# ESP32_USBC.net
KiCad netlist of a schematic drawn in Altium Designer
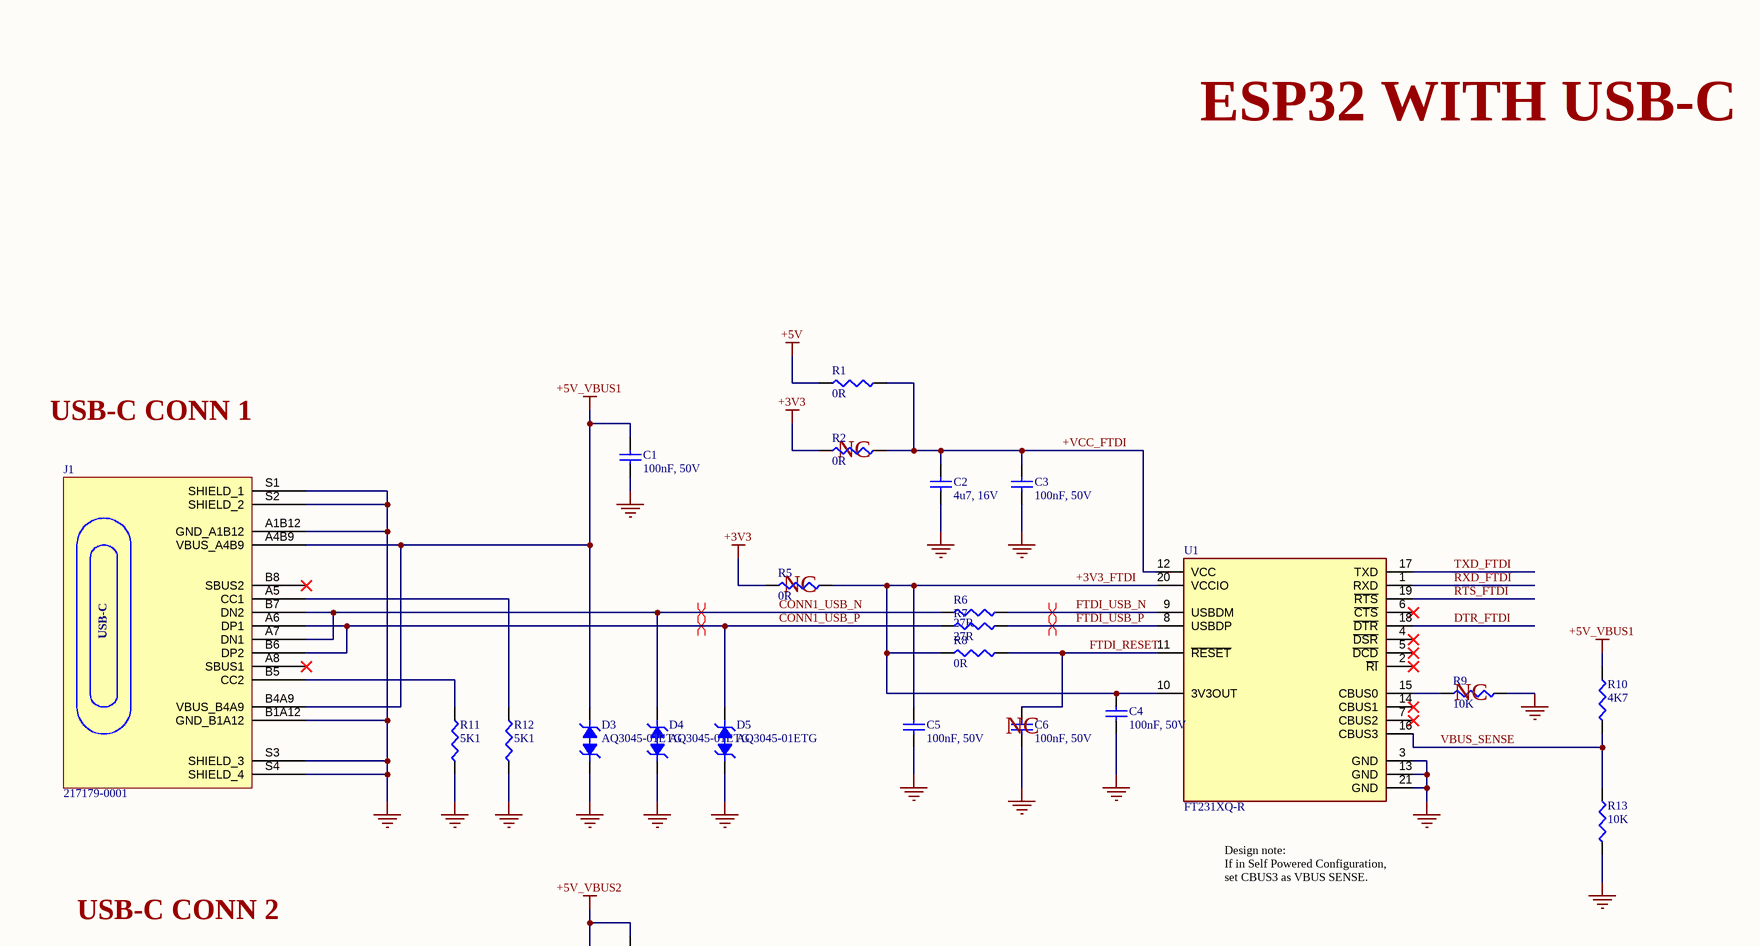
[diagram p0: ESP32_USBC.SchDoc, top left]
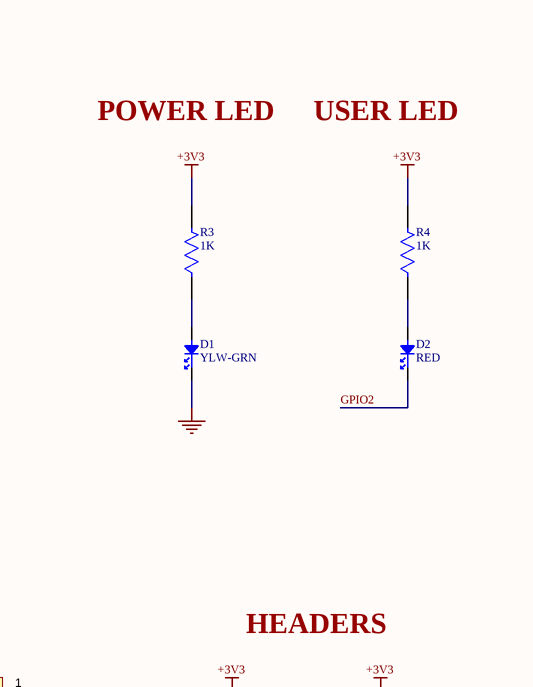
[diagram p1: ESP32_USBC.SchDoc, top right]
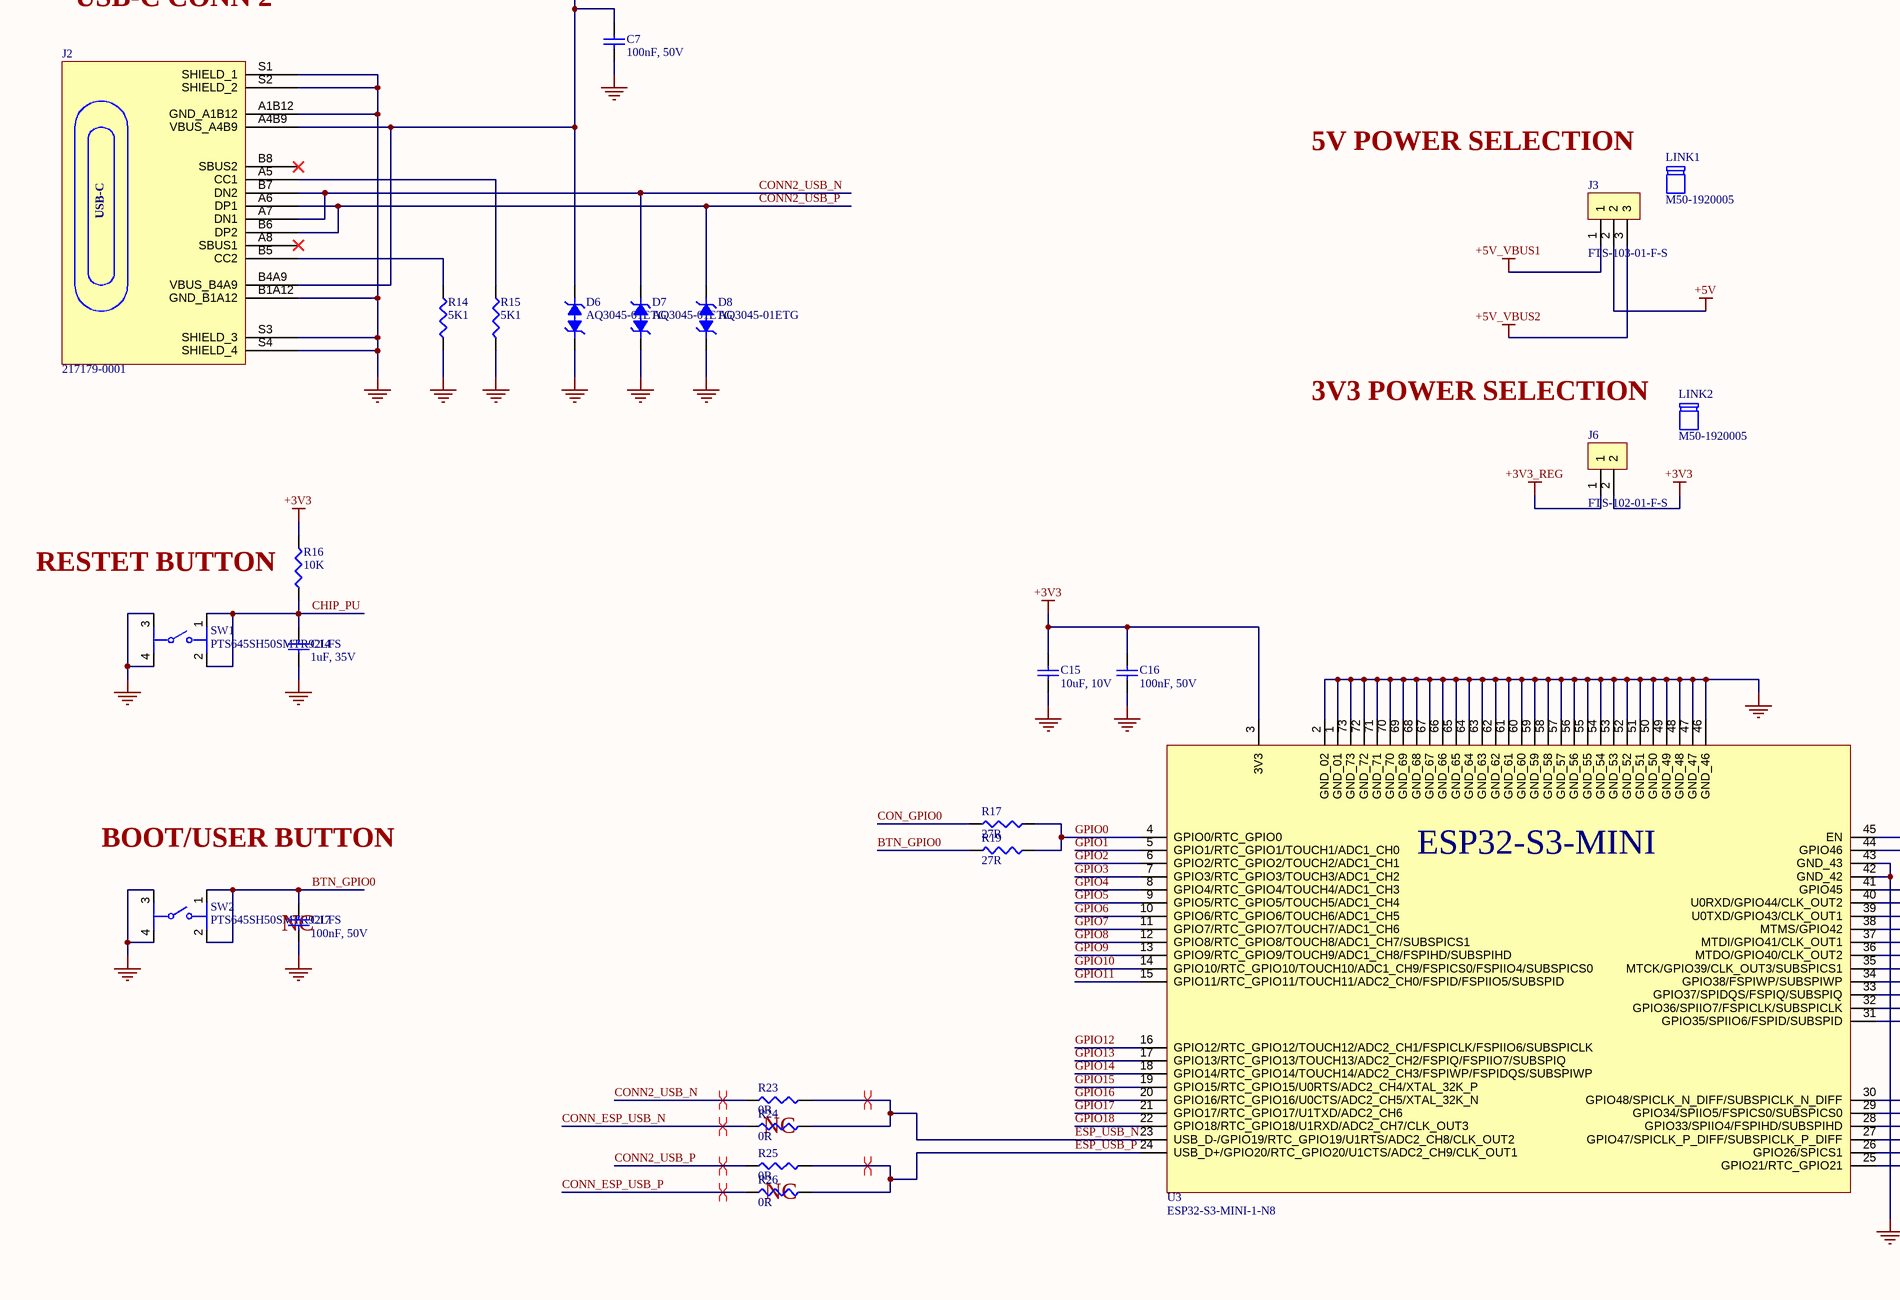
[diagram p2: ESP32_USBC.SchDoc, bottom left]
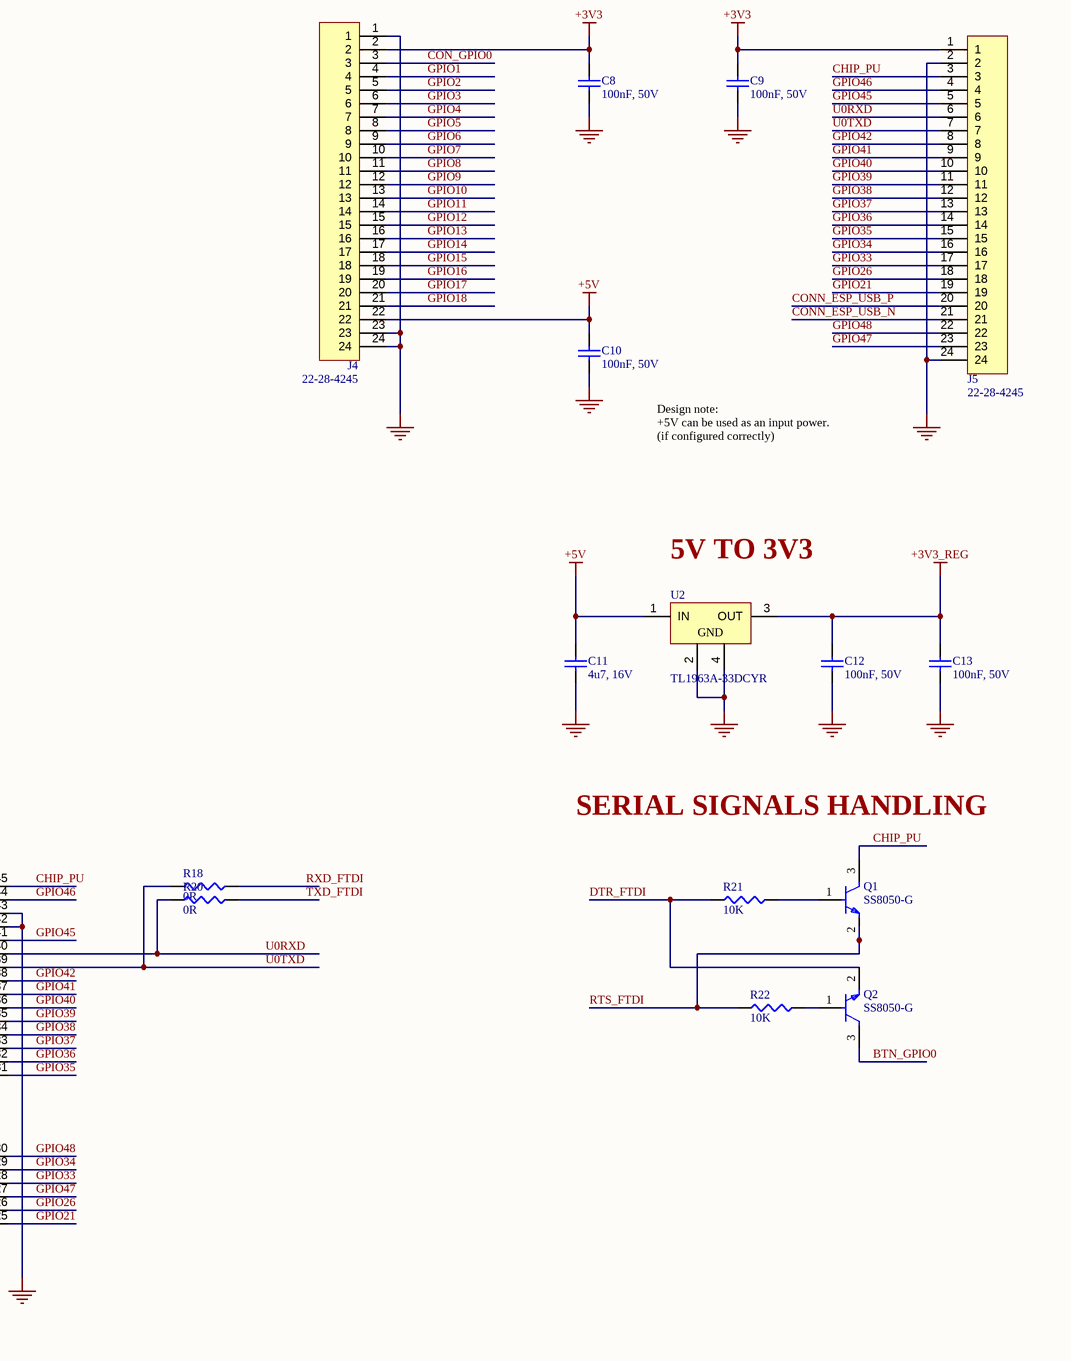
[diagram p3: ESP32_USBC.SchDoc, bottom right]

(export (version "E")
  (design (tool "Eeschema 10.0.6"))
  (components
    (comp (ref "C1")
      (value "100nF, 50V")
      (footprint "CAPC1005X65N")
      (description "CAP CER 0.1UF 50V X7R 0402")
      (fields
        (field (name "MANUFACTURER") "Samsung Electro-Mechanics")
        (field (name "MANUFACTURER PART NUMBER") "CL05B104KB5NNNC")
      )
      (libsource (lib "Schlib") (part "CL05B104KB5NNNC"))
    )
    (comp (ref "C2")
      (value "4u7, 16V")
      (footprint "CAPC1005X65N")
      (description "CAP CER 4.7UF 16V X5R 0402")
      (fields
        (field (name "MANUFACTURER") "Samsung Electro-Mechanics")
        (field (name "MANUFACTURER PART NUMBER") "CL05A475MO5NUNC")
      )
      (libsource (lib "Schlib") (part "CL05A475MO5NUNC"))
    )
    (comp (ref "C3")
      (value "100nF, 50V")
      (footprint "CAPC1005X65N")
      (description "CAP CER 0.1UF 50V X7R 0402")
      (fields
        (field (name "MANUFACTURER") "Samsung Electro-Mechanics")
        (field (name "MANUFACTURER PART NUMBER") "CL05B104KB5NNNC")
      )
      (libsource (lib "Schlib") (part "CL05B104KB5NNNC"))
    )
    (comp (ref "C4")
      (value "100nF, 50V")
      (footprint "CAPC1005X65N")
      (description "CAP CER 0.1UF 50V X7R 0402")
      (fields
        (field (name "MANUFACTURER") "Samsung Electro-Mechanics")
        (field (name "MANUFACTURER PART NUMBER") "CL05B104KB5NNNC")
      )
      (libsource (lib "Schlib") (part "CL05B104KB5NNNC"))
    )
    (comp (ref "C5")
      (value "100nF, 50V")
      (footprint "CAPC1005X65N")
      (description "CAP CER 0.1UF 50V X7R 0402")
      (fields
        (field (name "MANUFACTURER") "Samsung Electro-Mechanics")
        (field (name "MANUFACTURER PART NUMBER") "CL05B104KB5NNNC")
      )
      (libsource (lib "Schlib") (part "CL05B104KB5NNNC"))
    )
    (comp (ref "C6")
      (value "100nF, 50V")
      (footprint "CAPC1005X65N")
      (description "CAP CER 0.1UF 50V X7R 0402")
      (fields
        (field (name "MANUFACTURER") "Samsung Electro-Mechanics")
        (field (name "MANUFACTURER PART NUMBER") "CL05B104KB5NNNC")
      )
      (libsource (lib "Schlib") (part "CL05B104KB5NNNC"))
    )
    (comp (ref "C7")
      (value "100nF, 50V")
      (footprint "CAPC1005X65N")
      (description "CAP CER 0.1UF 50V X7R 0402")
      (fields
        (field (name "MANUFACTURER") "Samsung Electro-Mechanics")
        (field (name "MANUFACTURER PART NUMBER") "CL05B104KB5NNNC")
      )
      (libsource (lib "Schlib") (part "CL05B104KB5NNNC"))
    )
    (comp (ref "C8")
      (value "100nF, 50V")
      (footprint "CAPC1005X65N")
      (description "CAP CER 0.1UF 50V X7R 0402")
      (fields
        (field (name "MANUFACTURER") "Samsung Electro-Mechanics")
        (field (name "MANUFACTURER PART NUMBER") "CL05B104KB5NNNC")
      )
      (libsource (lib "Schlib") (part "CL05B104KB5NNNC"))
    )
    (comp (ref "C9")
      (value "100nF, 50V")
      (footprint "CAPC1005X65N")
      (description "CAP CER 0.1UF 50V X7R 0402")
      (fields
        (field (name "MANUFACTURER") "Samsung Electro-Mechanics")
        (field (name "MANUFACTURER PART NUMBER") "CL05B104KB5NNNC")
      )
      (libsource (lib "Schlib") (part "CL05B104KB5NNNC"))
    )
    (comp (ref "C10")
      (value "100nF, 50V")
      (footprint "CAPC1005X65N")
      (description "CAP CER 0.1UF 50V X7R 0402")
      (fields
        (field (name "MANUFACTURER") "Samsung Electro-Mechanics")
        (field (name "MANUFACTURER PART NUMBER") "CL05B104KB5NNNC")
      )
      (libsource (lib "Schlib") (part "CL05B104KB5NNNC"))
    )
    (comp (ref "C11")
      (value "4u7, 16V")
      (footprint "CAPC1005X65N")
      (description "CAP CER 4.7UF 16V X5R 0402")
      (fields
        (field (name "MANUFACTURER") "Samsung Electro-Mechanics")
        (field (name "MANUFACTURER PART NUMBER") "CL05A475MO5NUNC")
      )
      (libsource (lib "Schlib") (part "CL05A475MO5NUNC"))
    )
    (comp (ref "C12")
      (value "100nF, 50V")
      (footprint "CAPC1005X65N")
      (description "CAP CER 0.1UF 50V X7R 0402")
      (fields
        (field (name "MANUFACTURER") "Samsung Electro-Mechanics")
        (field (name "MANUFACTURER PART NUMBER") "CL05B104KB5NNNC")
      )
      (libsource (lib "Schlib") (part "CL05B104KB5NNNC"))
    )
    (comp (ref "C13")
      (value "100nF, 50V")
      (footprint "CAPC1005X65N")
      (description "CAP CER 0.1UF 50V X7R 0402")
      (fields
        (field (name "MANUFACTURER") "Samsung Electro-Mechanics")
        (field (name "MANUFACTURER PART NUMBER") "CL05B104KB5NNNC")
      )
      (libsource (lib "Schlib") (part "CL05B104KB5NNNC"))
    )
    (comp (ref "C14")
      (value "1uF, 35V")
      (footprint "CAPC1005X65N")
      (description "CAP CER 1UF 35V X5R 0402")
      (fields
        (field (name "MANUFACTURER") "Samsung Electro-Mechanics")
        (field (name "MANUFACTURER PART NUMBER") "CL05A105KL5NRNC")
      )
      (libsource (lib "Schlib") (part "CL05A105KL5NRNC"))
    )
    (comp (ref "C15")
      (value "10uF, 10V")
      (footprint "CAPC1005X65N")
      (description "CAP CER 10UF 10V X5R 0402")
      (fields
        (field (name "MANUFACTURER") "Samsung Electro-Mechanics")
        (field (name "MANUFACTURER PART NUMBER") "CL05A106MP8NUB8")
      )
      (libsource (lib "Schlib") (part "CL05A106MP8NUB8"))
    )
    (comp (ref "C16")
      (value "100nF, 50V")
      (footprint "CAPC1005X65N")
      (description "CAP CER 0.1UF 50V X7R 0402")
      (fields
        (field (name "MANUFACTURER") "Samsung Electro-Mechanics")
        (field (name "MANUFACTURER PART NUMBER") "CL05B104KB5NNNC")
      )
      (libsource (lib "Schlib") (part "CL05B104KB5NNNC"))
    )
    (comp (ref "C17")
      (value "100nF, 50V")
      (footprint "CAPC1005X65N")
      (description "CAP CER 0.1UF 50V X7R 0402")
      (fields
        (field (name "MANUFACTURER") "Samsung Electro-Mechanics")
        (field (name "MANUFACTURER PART NUMBER") "CL05B104KB5NNNC")
      )
      (libsource (lib "Schlib") (part "CL05B104KB5NNNC"))
    )
    (comp (ref "D1")
      (value "YLW-GRN")
      (footprint "LED0402G")
      (description "LED YLW-GRN 0402 SMD")
      (fields
        (field (name "MANUFACTURER") "Vishay")
        (field (name "MANUFACTURER PART NUMBER") "VLMG1500-GS08")
      )
      (libsource (lib "Schlib") (part "VLMG1500-GS08"))
    )
    (comp (ref "D2")
      (value "RED")
      (footprint "LED0402R")
      (description "LED RED 0402 SMD")
      (fields
        (field (name "MANUFACTURER") "Vishay")
        (field (name "MANUFACTURER PART NUMBER") "VLMS1500-GS08")
      )
      (libsource (lib "Schlib") (part "VLMS1500-GS08"))
    )
    (comp (ref "D3")
      (value "AQ3045-01ETG")
      (footprint "SOD882")
      (description "TVS DIODE 5.3VWM 12VC SOD882")
      (fields (field (name "MANUFACTURER") "Littelfuse") (field (name "LCSC PART NUMBER") "C3710326"))
      (libsource (lib "Schlib") (part "AQ3045-01ETG"))
    )
    (comp (ref "D4")
      (value "AQ3045-01ETG")
      (footprint "SOD882")
      (description "TVS DIODE 5.3VWM 12VC SOD882")
      (fields (field (name "MANUFACTURER") "Littelfuse") (field (name "LCSC PART NUMBER") "C3710326"))
      (libsource (lib "Schlib") (part "AQ3045-01ETG"))
    )
    (comp (ref "D5")
      (value "AQ3045-01ETG")
      (footprint "SOD882")
      (description "TVS DIODE 5.3VWM 12VC SOD882")
      (fields (field (name "MANUFACTURER") "Littelfuse") (field (name "LCSC PART NUMBER") "C3710326"))
      (libsource (lib "Schlib") (part "AQ3045-01ETG"))
    )
    (comp (ref "D6")
      (value "AQ3045-01ETG")
      (footprint "SOD882")
      (description "TVS DIODE 5.3VWM 12VC SOD882")
      (fields (field (name "MANUFACTURER") "Littelfuse") (field (name "LCSC PART NUMBER") "C3710326"))
      (libsource (lib "Schlib") (part "AQ3045-01ETG"))
    )
    (comp (ref "D7")
      (value "AQ3045-01ETG")
      (footprint "SOD882")
      (description "TVS DIODE 5.3VWM 12VC SOD882")
      (fields (field (name "MANUFACTURER") "Littelfuse") (field (name "LCSC PART NUMBER") "C3710326"))
      (libsource (lib "Schlib") (part "AQ3045-01ETG"))
    )
    (comp (ref "D8")
      (value "AQ3045-01ETG")
      (footprint "SOD882")
      (description "TVS DIODE 5.3VWM 12VC SOD882")
      (fields (field (name "MANUFACTURER") "Littelfuse") (field (name "LCSC PART NUMBER") "C3710326"))
      (libsource (lib "Schlib") (part "AQ3045-01ETG"))
    )
    (comp (ref "J1")
      (value "217179-0001")
      (footprint "FP-2171790001-MFG")
      (description "CONN RCP USB2.0 TYP C 24P SMD RA")
      (fields (field (name "MANUFACTURER") "Molex") (field (name "LCSC PART NUMBER") "C3197684"))
      (libsource (lib "Schlib") (part "217179-0001"))
    )
    (comp (ref "J2")
      (value "217179-0001")
      (footprint "FP-2171790001-MFG")
      (description "CONN RCP USB2.0 TYP C 24P SMD RA")
      (fields (field (name "MANUFACTURER") "Molex") (field (name "LCSC PART NUMBER") "C3197684"))
      (libsource (lib "Schlib") (part "217179-0001"))
    )
    (comp (ref "J3")
      (value "FTS-103-01-F-S")
      (footprint "HDR_1X3_1.27MM")
      (description "CONN HEADER VERT 3POS 1.27MM")
      (fields (field (name "MANUFACTURER") "Samtec") (field (name "LCSC PART NUMBER") "C3333578"))
      (libsource (lib "Schlib") (part "FTS-103-01-F-S"))
    )
    (comp (ref "J4")
      (value "22-28-4245")
      (footprint "HDR_1X24_2.54MM")
      (description "Connector Header Through Hole 24 position 0.100\" (2.54mm)")
      (fields (field (name "MANUFACTURER") "Molex") (field (name "LCSC PART NUMBER") "C7145888"))
      (libsource (lib "Schlib") (part "22-28-4245"))
    )
    (comp (ref "J5")
      (value "22-28-4245")
      (footprint "HDR_1X24_2.54MM")
      (description "Connector Header Through Hole 24 position 0.100\" (2.54mm)")
      (fields (field (name "MANUFACTURER") "Molex") (field (name "LCSC PART NUMBER") "C7145888"))
      (libsource (lib "") (part "22-28-4245_1"))
    )
    (comp (ref "J6")
      (value "FTS-102-01-F-S")
      (footprint "HDR_1X2_1.27MM")
      (description "CONN HEADER VERT 2POS 1.27 MM")
      (fields (field (name "MANUFACTURER") "Samtec") (field (name "LCSC PART NUMBER") "C6045317"))
      (libsource (lib "Schlib") (part "FTS-102-01-F-S"))
    )
    (comp (ref "LINK1")
      (value "M50-1920005")
      (description "CONN SHUNT 1.27MM RED")
      (fields (field (name "MANUFACTURER") "Harwin") (field (name "LCSC PART NUMBER") "C6985646"))
      (libsource (lib "Schlib") (part "M50-1920005"))
    )
    (comp (ref "LINK2")
      (value "M50-1920005")
      (description "CONN SHUNT 1.27MM RED")
      (fields (field (name "MANUFACTURER") "Harwin") (field (name "LCSC PART NUMBER") "C6985646"))
      (libsource (lib "Schlib") (part "M50-1920005"))
    )
    (comp (ref "Q1")
      (value "SS8050-G")
      (footprint "FP-SS8050-G-IPC_B")
      (description "TRANS NPN 25V 1.5A SOT-23-3")
      (fields (field (name "MANUFACTURER") "Comchip") (field (name "LCSC PART NUMBER") "C164886"))
      (libsource (lib "Schlib") (part "SS8050-G"))
    )
    (comp (ref "Q2")
      (value "SS8050-G")
      (footprint "FP-SS8050-G-IPC_B")
      (description "TRANS NPN 25V 1.5A SOT-23-3")
      (fields (field (name "MANUFACTURER") "Comchip") (field (name "LCSC PART NUMBER") "C164886"))
      (libsource (lib "Schlib") (part "SS8050-G"))
    )
    (comp (ref "R1")
      (value "0R")
      (footprint "RESC1005X37N")
      (description "RES 0 OHM JUMPER 1/16W 0402")
      (fields
        (field (name "MANUFACTURER") "Yageo Group")
        (field (name "MANUFACTURER PART NUMBER") "RC0402JR-070RL")
      )
      (libsource (lib "Schlib") (part "RC0402JR-070RL"))
    )
    (comp (ref "R2")
      (value "0R")
      (footprint "RESC1005X37N")
      (description "RES 0 OHM JUMPER 1/16W 0402")
      (fields
        (field (name "MANUFACTURER") "Yageo Group")
        (field (name "MANUFACTURER PART NUMBER") "RC0402JR-070RL")
      )
      (libsource (lib "Schlib") (part "RC0402JR-070RL"))
    )
    (comp (ref "R3")
      (value "1K")
      (footprint "RESC1005X37N")
      (description "RES 1K OHM 1% 1/16W 0402")
      (fields
        (field (name "MANUFACTURER") "Yageo Group")
        (field (name "MANUFACTURER PART NUMBER") "RC0402FR-071KL")
      )
      (libsource (lib "Schlib") (part "RC0402FR-071KL"))
    )
    (comp (ref "R4")
      (value "1K")
      (footprint "RESC1005X37N")
      (description "RES 1K OHM 1% 1/16W 0402")
      (fields
        (field (name "MANUFACTURER") "Yageo Group")
        (field (name "MANUFACTURER PART NUMBER") "RC0402FR-071KL")
      )
      (libsource (lib "Schlib") (part "RC0402FR-071KL"))
    )
    (comp (ref "R5")
      (value "0R")
      (footprint "RESC1005X37N")
      (description "RES 0 OHM JUMPER 1/16W 0402")
      (fields
        (field (name "MANUFACTURER") "Yageo Group")
        (field (name "MANUFACTURER PART NUMBER") "RC0402JR-070RL")
      )
      (libsource (lib "Schlib") (part "RC0402JR-070RL"))
    )
    (comp (ref "R6")
      (value "27R")
      (footprint "RESC1005X37N")
      (description "RES 27 OHM 1% 1/16W 0402")
      (fields
        (field (name "MANUFACTURER") "Yageo Group")
        (field (name "MANUFACTURER PART NUMBER") "RC0402FR-0727RL")
      )
      (libsource (lib "Schlib") (part "RC0402FR-0727RL"))
    )
    (comp (ref "R7")
      (value "27R")
      (footprint "RESC1005X37N")
      (description "RES 27 OHM 1% 1/16W 0402")
      (fields
        (field (name "MANUFACTURER") "Yageo Group")
        (field (name "MANUFACTURER PART NUMBER") "RC0402FR-0727RL")
      )
      (libsource (lib "Schlib") (part "RC0402FR-0727RL"))
    )
    (comp (ref "R8")
      (value "0R")
      (footprint "RESC1005X37N")
      (description "RES 0 OHM JUMPER 1/16W 0402")
      (fields
        (field (name "MANUFACTURER") "Yageo Group")
        (field (name "MANUFACTURER PART NUMBER") "RC0402JR-070RL")
      )
      (libsource (lib "Schlib") (part "RC0402JR-070RL"))
    )
    (comp (ref "R9")
      (value "10K")
      (footprint "RESC1005X37N")
      (description "RES SMD 10K OHM 1% 1/16W 0402")
      (fields
        (field (name "MANUFACTURER") "Yageo Group")
        (field (name "MANUFACTURER PART NUMBER") "AC0402FR-0710KL")
      )
      (libsource (lib "Schlib") (part "AC0402FR-0710KL"))
    )
    (comp (ref "R10")
      (value "4K7")
      (footprint "RESC1005X37N")
      (description "RES 4.7K OHM 1% 1/16W 0402")
      (fields
        (field (name "MANUFACTURER") "Yageo Group")
        (field (name "MANUFACTURER PART NUMBER") "RC0402FR-074K7L")
      )
      (libsource (lib "Schlib") (part "RC0402FR-074K7L"))
    )
    (comp (ref "R11")
      (value "5K1")
      (footprint "RESC1005X37N")
      (description "RES SMD 5.1K OHM 1% 1/16W 0402")
      (fields
        (field (name "MANUFACTURER") "Yageo Group")
        (field (name "MANUFACTURER PART NUMBER") "AC0402FR-075K1L")
      )
      (libsource (lib "Schlib") (part "AC0402FR-075K1L"))
    )
    (comp (ref "R12")
      (value "5K1")
      (footprint "RESC1005X37N")
      (description "RES SMD 5.1K OHM 1% 1/16W 0402")
      (fields
        (field (name "MANUFACTURER") "Yageo Group")
        (field (name "MANUFACTURER PART NUMBER") "AC0402FR-075K1L")
      )
      (libsource (lib "Schlib") (part "AC0402FR-075K1L"))
    )
    (comp (ref "R13")
      (value "10K")
      (footprint "RESC1005X37N")
      (description "RES SMD 10K OHM 1% 1/16W 0402")
      (fields
        (field (name "MANUFACTURER") "Yageo Group")
        (field (name "MANUFACTURER PART NUMBER") "AC0402FR-0710KL")
      )
      (libsource (lib "Schlib") (part "AC0402FR-0710KL"))
    )
    (comp (ref "R14")
      (value "5K1")
      (footprint "RESC1005X37N")
      (description "RES SMD 5.1K OHM 1% 1/16W 0402")
      (fields
        (field (name "MANUFACTURER") "Yageo Group")
        (field (name "MANUFACTURER PART NUMBER") "AC0402FR-075K1L")
      )
      (libsource (lib "Schlib") (part "AC0402FR-075K1L"))
    )
    (comp (ref "R15")
      (value "5K1")
      (footprint "RESC1005X37N")
      (description "RES SMD 5.1K OHM 1% 1/16W 0402")
      (fields
        (field (name "MANUFACTURER") "Yageo Group")
        (field (name "MANUFACTURER PART NUMBER") "AC0402FR-075K1L")
      )
      (libsource (lib "Schlib") (part "AC0402FR-075K1L"))
    )
    (comp (ref "R16")
      (value "10K")
      (footprint "RESC1005X37N")
      (description "RES SMD 10K OHM 1% 1/16W 0402")
      (fields
        (field (name "MANUFACTURER") "Yageo Group")
        (field (name "MANUFACTURER PART NUMBER") "AC0402FR-0710KL")
      )
      (libsource (lib "Schlib") (part "AC0402FR-0710KL"))
    )
    (comp (ref "R17")
      (value "27R")
      (footprint "RESC1005X37N")
      (description "RES 27 OHM 1% 1/16W 0402")
      (fields
        (field (name "MANUFACTURER") "Yageo Group")
        (field (name "MANUFACTURER PART NUMBER") "RC0402FR-0727RL")
      )
      (libsource (lib "Schlib") (part "RC0402FR-0727RL"))
    )
    (comp (ref "R18")
      (value "0R")
      (footprint "RESC1005X37N")
      (description "RES 0 OHM JUMPER 1/16W 0402")
      (fields
        (field (name "MANUFACTURER") "Yageo Group")
        (field (name "MANUFACTURER PART NUMBER") "RC0402JR-070RL")
      )
      (libsource (lib "Schlib") (part "RC0402JR-070RL"))
    )
    (comp (ref "R19")
      (value "27R")
      (footprint "RESC1005X37N")
      (description "RES 27 OHM 1% 1/16W 0402")
      (fields
        (field (name "MANUFACTURER") "Yageo Group")
        (field (name "MANUFACTURER PART NUMBER") "RC0402FR-0727RL")
      )
      (libsource (lib "Schlib") (part "RC0402FR-0727RL"))
    )
    (comp (ref "R20")
      (value "0R")
      (footprint "RESC1005X37N")
      (description "RES 0 OHM JUMPER 1/16W 0402")
      (fields
        (field (name "MANUFACTURER") "Yageo Group")
        (field (name "MANUFACTURER PART NUMBER") "RC0402JR-070RL")
      )
      (libsource (lib "Schlib") (part "RC0402JR-070RL"))
    )
    (comp (ref "R21")
      (value "10K")
      (footprint "RESC1005X37N")
      (description "RES SMD 10K OHM 1% 1/16W 0402")
      (fields
        (field (name "MANUFACTURER") "Yageo Group")
        (field (name "MANUFACTURER PART NUMBER") "AC0402FR-0710KL")
      )
      (libsource (lib "Schlib") (part "AC0402FR-0710KL"))
    )
    (comp (ref "R22")
      (value "10K")
      (footprint "RESC1005X37N")
      (description "RES SMD 10K OHM 1% 1/16W 0402")
      (fields
        (field (name "MANUFACTURER") "Yageo Group")
        (field (name "MANUFACTURER PART NUMBER") "AC0402FR-0710KL")
      )
      (libsource (lib "Schlib") (part "AC0402FR-0710KL"))
    )
    (comp (ref "R23")
      (value "0R")
      (footprint "RESC1005X37N")
      (description "RES 0 OHM JUMPER 1/16W 0402")
      (fields
        (field (name "MANUFACTURER") "Yageo Group")
        (field (name "MANUFACTURER PART NUMBER") "RC0402JR-070RL")
      )
      (libsource (lib "Schlib") (part "RC0402JR-070RL"))
    )
    (comp (ref "R24")
      (value "0R")
      (footprint "RESC1005X37N")
      (description "RES 0 OHM JUMPER 1/16W 0402")
      (fields
        (field (name "MANUFACTURER") "Yageo Group")
        (field (name "MANUFACTURER PART NUMBER") "RC0402JR-070RL")
      )
      (libsource (lib "Schlib") (part "RC0402JR-070RL"))
    )
    (comp (ref "R25")
      (value "0R")
      (footprint "RESC1005X37N")
      (description "RES 0 OHM JUMPER 1/16W 0402")
      (fields
        (field (name "MANUFACTURER") "Yageo Group")
        (field (name "MANUFACTURER PART NUMBER") "RC0402JR-070RL")
      )
      (libsource (lib "Schlib") (part "RC0402JR-070RL"))
    )
    (comp (ref "R26")
      (value "0R")
      (footprint "RESC1005X37N")
      (description "RES 0 OHM JUMPER 1/16W 0402")
      (fields
        (field (name "MANUFACTURER") "Yageo Group")
        (field (name "MANUFACTURER PART NUMBER") "RC0402JR-070RL")
      )
      (libsource (lib "Schlib") (part "RC0402JR-070RL"))
    )
    (comp (ref "SW1")
      (value "PTS645SH50SMTR92LFS")
      (footprint "FP-PTS645SH50SMTR92LFS-MFG")
      (description "SWITCH TACTILE SPST-NO 0.05A 12V")
      (fields (field (name "MANUFACTURER") "C&K Components") (field (name "LCSC PART NUMBER") "C144807"))
      (libsource (lib "Schlib") (part "PTS645SH50SMTR92LFS"))
    )
    (comp (ref "SW2")
      (value "PTS645SH50SMTR92LFS")
      (footprint "FP-PTS645SH50SMTR92LFS-MFG")
      (description "SWITCH TACTILE SPST-NO 0.05A 12V")
      (fields (field (name "MANUFACTURER") "C&K Components") (field (name "LCSC PART NUMBER") "C144807"))
      (libsource (lib "Schlib") (part "PTS645SH50SMTR92LFS"))
    )
    (comp (ref "U1")
      (value "FT231XQ-R")
      (footprint "FP-QFN-20-IPC_B")
      (description "IC USB SERIAL FULL UART 20QFN")
      (fields (field (name "MANUFACTURER") "FTDI") (field (name "LCSC PART NUMBER") "C132159"))
      (libsource (lib "Schlib") (part "FT231XQ-R"))
    )
    (comp (ref "U2")
      (value "TL1963A-33DCYR")
      (footprint "DCY0004A_N")
      (description "IC REG LIN 3.3V 1.5A SOT-223-4")
      (fields (field (name "MANUFACTURER") "Texas Instruments") (field (name "LCSC PART NUMBER") "C181262"))
      (libsource (lib "Schlib") (part "TL1963A-33DCYR"))
    )
    (comp (ref "U3")
      (value "ESP32-S3-MINI-1-N8")
      (footprint "XCVR_ESP32-S3-MINI-1-N8")
      (description "20.5dBm ESP32-S3FN8 Chip 2.4GHz SMD WiFi Modules ROHS")
      (fields (field (name "MANUFACTURER") "Espressif Systems") (field (name "LCSC PART NUMBER") "C2913206"))
      (libsource (lib "Schlib") (part "ESP32-S3-MINI-1-N8"))
    )
  )
  (nets
    (net (code "1") (name "+3V3") (class "Default")
      (node (ref "C15") (pin "2") (pinfunction "2_2") (pintype "passive"))
      (node (ref "C16") (pin "2") (pinfunction "2_2") (pintype "passive"))
      (node (ref "C8") (pin "2") (pinfunction "2_2") (pintype "passive"))
      (node (ref "C9") (pin "2") (pinfunction "2_2") (pintype "passive"))
      (node (ref "J4") (pin "2") (pinfunction "2_2") (pintype "passive"))
      (node (ref "J5") (pin "1") (pinfunction "1_1") (pintype "passive"))
      (node (ref "J6") (pin "2") (pinfunction "2_2") (pintype "passive"))
      (node (ref "R16") (pin "2") (pinfunction "2_2") (pintype "passive"))
      (node (ref "R2") (pin "1") (pinfunction "1_1") (pintype "passive"))
      (node (ref "R3") (pin "2") (pinfunction "2_2") (pintype "passive"))
      (node (ref "R4") (pin "2") (pinfunction "2_2") (pintype "passive"))
      (node (ref "R5") (pin "1") (pinfunction "1_1") (pintype "passive"))
      (node (ref "U3") (pin "3") (pinfunction "3V3_3") (pintype "passive"))
    )
    (net (code "2") (name "+3V3_REG") (class "Default")
      (node (ref "C12") (pin "2") (pinfunction "2_2") (pintype "passive"))
      (node (ref "C13") (pin "2") (pinfunction "2_2") (pintype "passive"))
      (node (ref "J6") (pin "1") (pinfunction "1_1") (pintype "passive"))
      (node (ref "U2") (pin "3") (pinfunction "OUT_3") (pintype "power_in"))
    )
    (net (code "3") (name "+5V") (class "Default")
      (node (ref "C10") (pin "2") (pinfunction "2_2") (pintype "passive"))
      (node (ref "C11") (pin "2") (pinfunction "2_2") (pintype "passive"))
      (node (ref "J3") (pin "2") (pinfunction "2_2") (pintype "passive"))
      (node (ref "J4") (pin "22") (pinfunction "22_22") (pintype "passive"))
      (node (ref "R1") (pin "1") (pinfunction "1_1") (pintype "passive"))
      (node (ref "U2") (pin "1") (pinfunction "IN_1") (pintype "power_in"))
    )
    (net (code "4") (name "+5V_VBUS1") (class "Default")
      (node (ref "C1") (pin "2") (pinfunction "2_2") (pintype "passive"))
      (node (ref "D3") (pin "2") (pinfunction "2_2") (pintype "passive"))
      (node (ref "J1") (pin "A4B9") (pinfunction "VBUS_A4B9_A4B9") (pintype "passive"))
      (node (ref "J1") (pin "B4A9") (pinfunction "VBUS_B4A9_B4A9") (pintype "passive"))
      (node (ref "J3") (pin "1") (pinfunction "1_1") (pintype "passive"))
      (node (ref "R10") (pin "2") (pinfunction "2_2") (pintype "passive"))
    )
    (net (code "5") (name "+5V_VBUS2") (class "Default")
      (node (ref "C7") (pin "2") (pinfunction "2_2") (pintype "passive"))
      (node (ref "D6") (pin "2") (pinfunction "2_2") (pintype "passive"))
      (node (ref "J2") (pin "A4B9") (pinfunction "VBUS_A4B9_A4B9") (pintype "passive"))
      (node (ref "J2") (pin "B4A9") (pinfunction "VBUS_B4A9_B4A9") (pintype "passive"))
      (node (ref "J3") (pin "3") (pinfunction "3_3") (pintype "passive"))
    )
    (net (code "6") (name "/+3V3_FTDI") (class "Default")
      (node (ref "C4") (pin "1") (pinfunction "1_1") (pintype "passive"))
      (node (ref "C5") (pin "1") (pinfunction "1_1") (pintype "passive"))
      (node (ref "R5") (pin "2") (pinfunction "2_2") (pintype "passive"))
      (node (ref "R8") (pin "1") (pinfunction "1_1") (pintype "passive"))
      (node (ref "U1") (pin "10") (pinfunction "3V3OUT_10") (pintype "passive"))
      (node (ref "U1") (pin "20") (pinfunction "VCCIO_20") (pintype "passive"))
    )
    (net (code "7") (name "/+VCC_FTDI") (class "Default")
      (node (ref "C2") (pin "2") (pinfunction "2_2") (pintype "passive"))
      (node (ref "C3") (pin "1") (pinfunction "1_1") (pintype "passive"))
      (node (ref "R1") (pin "2") (pinfunction "2_2") (pintype "passive"))
      (node (ref "R2") (pin "2") (pinfunction "2_2") (pintype "passive"))
      (node (ref "U1") (pin "12") (pinfunction "VCC_12") (pintype "passive"))
    )
    (net (code "8") (name "/BTN_GPIO0") (class "Default")
      (node (ref "C17") (pin "2") (pinfunction "2_2") (pintype "passive"))
      (node (ref "Q2") (pin "3") (pinfunction "C_3") (pintype "passive"))
      (node (ref "R19") (pin "2") (pinfunction "2_2") (pintype "passive"))
      (node (ref "SW2") (pin "1") (pinfunction "1_1") (pintype "passive"))
      (node (ref "SW2") (pin "2") (pinfunction "2_2") (pintype "passive"))
    )
    (net (code "9") (name "/CHIP_PU") (class "Default")
      (node (ref "C14") (pin "2") (pinfunction "2_2") (pintype "passive"))
      (node (ref "J5") (pin "3") (pinfunction "3_3") (pintype "passive"))
      (node (ref "Q1") (pin "3") (pinfunction "C_3") (pintype "passive"))
      (node (ref "R16") (pin "1") (pinfunction "1_1") (pintype "passive"))
      (node (ref "SW1") (pin "1") (pinfunction "1_1") (pintype "passive"))
      (node (ref "SW1") (pin "2") (pinfunction "2_2") (pintype "passive"))
      (node (ref "U3") (pin "45") (pinfunction "EN_45") (pintype "passive"))
    )
    (net (code "10") (name "/CONN1_USB_N") (class "Default")
      (node (ref "D4") (pin "2") (pinfunction "2_2") (pintype "passive"))
      (node (ref "J1") (pin "A7") (pinfunction "DN1_A7") (pintype "passive"))
      (node (ref "J1") (pin "B7") (pinfunction "DN2_B7") (pintype "passive"))
      (node (ref "R6") (pin "2") (pinfunction "2_2") (pintype "passive"))
    )
    (net (code "11") (name "/CONN1_USB_P") (class "Default")
      (node (ref "D5") (pin "2") (pinfunction "2_2") (pintype "passive"))
      (node (ref "J1") (pin "A6") (pinfunction "DP1_A6") (pintype "passive"))
      (node (ref "J1") (pin "B6") (pinfunction "DP2_B6") (pintype "passive"))
      (node (ref "R7") (pin "2") (pinfunction "2_2") (pintype "passive"))
    )
    (net (code "12") (name "/CONN2_USB_N") (class "Default")
      (node (ref "D7") (pin "2") (pinfunction "2_2") (pintype "passive"))
      (node (ref "J2") (pin "A7") (pinfunction "DN1_A7") (pintype "passive"))
      (node (ref "J2") (pin "B7") (pinfunction "DN2_B7") (pintype "passive"))
      (node (ref "R23") (pin "1") (pinfunction "1_1") (pintype "passive"))
    )
    (net (code "13") (name "/CONN2_USB_P") (class "Default")
      (node (ref "D8") (pin "2") (pinfunction "2_2") (pintype "passive"))
      (node (ref "J2") (pin "A6") (pinfunction "DP1_A6") (pintype "passive"))
      (node (ref "J2") (pin "B6") (pinfunction "DP2_B6") (pintype "passive"))
      (node (ref "R25") (pin "1") (pinfunction "1_1") (pintype "passive"))
    )
    (net (code "14") (name "/CONN_ESP_USB_N") (class "Default")
      (node (ref "J5") (pin "21") (pinfunction "21_21") (pintype "passive"))
      (node (ref "R24") (pin "1") (pinfunction "1_1") (pintype "passive"))
    )
    (net (code "15") (name "/CONN_ESP_USB_P") (class "Default")
      (node (ref "J5") (pin "20") (pinfunction "20_20") (pintype "passive"))
      (node (ref "R26") (pin "1") (pinfunction "1_1") (pintype "passive"))
    )
    (net (code "16") (name "/CON_GPIO0") (class "Default")
      (node (ref "J4") (pin "3") (pinfunction "3_3") (pintype "passive"))
      (node (ref "R17") (pin "2") (pinfunction "2_2") (pintype "passive"))
    )
    (net (code "17") (name "/DTR_FTDI") (class "Default")
      (node (ref "Q2") (pin "2") (pinfunction "E_2") (pintype "passive"))
      (node (ref "R21") (pin "2") (pinfunction "2_2") (pintype "passive"))
      (node (ref "U1") (pin "18") (pinfunction "~{DTR}_18") (pintype "passive"))
    )
    (net (code "18") (name "/ESP_USB_N") (class "Default")
      (node (ref "R23") (pin "2") (pinfunction "2_2") (pintype "passive"))
      (node (ref "R24") (pin "2") (pinfunction "2_2") (pintype "passive"))
      (node (ref "U3") (pin "23") (pinfunction "USB_D-/GPIO19/RTC_GPIO19/U1RTS/ADC2_CH8/CLK_OUT2_23") (pintype "passive"))
    )
    (net (code "19") (name "/ESP_USB_P") (class "Default")
      (node (ref "R25") (pin "2") (pinfunction "2_2") (pintype "passive"))
      (node (ref "R26") (pin "2") (pinfunction "2_2") (pintype "passive"))
      (node (ref "U3") (pin "24") (pinfunction "USB_D+/GPIO20/RTC_GPIO20/U1CTS/ADC2_CH9/CLK_OUT1_24") (pintype "passive"))
    )
    (net (code "20") (name "/FTDI_RESET") (class "Default")
      (node (ref "C6") (pin "1") (pinfunction "1_1") (pintype "passive"))
      (node (ref "R8") (pin "2") (pinfunction "2_2") (pintype "passive"))
      (node (ref "U1") (pin "11") (pinfunction "~{RESET}_11") (pintype "passive"))
    )
    (net (code "21") (name "/FTDI_USB_N") (class "Default")
      (node (ref "R6") (pin "1") (pinfunction "1_1") (pintype "passive"))
      (node (ref "U1") (pin "9") (pinfunction "USBDM_9") (pintype "passive"))
    )
    (net (code "22") (name "/FTDI_USB_P") (class "Default")
      (node (ref "R7") (pin "1") (pinfunction "1_1") (pintype "passive"))
      (node (ref "U1") (pin "8") (pinfunction "USBDP_8") (pintype "passive"))
    )
    (net (code "23") (name "/GPIO0") (class "Default")
      (node (ref "R17") (pin "1") (pinfunction "1_1") (pintype "passive"))
      (node (ref "R19") (pin "1") (pinfunction "1_1") (pintype "passive"))
      (node (ref "U3") (pin "4") (pinfunction "GPIO0/RTC_GPIO0_4") (pintype "passive"))
    )
    (net (code "24") (name "/GPIO1") (class "Default")
      (node (ref "J4") (pin "4") (pinfunction "4_4") (pintype "passive"))
      (node (ref "U3") (pin "5") (pinfunction "GPIO1/RTC_GPIO1/TOUCH1/ADC1_CH0_5") (pintype "passive"))
    )
    (net (code "25") (name "/GPIO2") (class "Default")
      (node (ref "D2") (pin "1") (pinfunction "1_1") (pintype "passive"))
      (node (ref "J4") (pin "5") (pinfunction "5_5") (pintype "passive"))
      (node (ref "U3") (pin "6") (pinfunction "GPIO2/RTC_GPIO2/TOUCH2/ADC1_CH1_6") (pintype "passive"))
    )
    (net (code "26") (name "/GPIO3") (class "Default")
      (node (ref "J4") (pin "6") (pinfunction "6_6") (pintype "passive"))
      (node (ref "U3") (pin "7") (pinfunction "GPIO3/RTC_GPIO3/TOUCH3/ADC1_CH2_7") (pintype "passive"))
    )
    (net (code "27") (name "/GPIO4") (class "Default")
      (node (ref "J4") (pin "7") (pinfunction "7_7") (pintype "passive"))
      (node (ref "U3") (pin "8") (pinfunction "GPIO4/RTC_GPIO4/TOUCH4/ADC1_CH3_8") (pintype "passive"))
    )
    (net (code "28") (name "/GPIO5") (class "Default")
      (node (ref "J4") (pin "8") (pinfunction "8_8") (pintype "passive"))
      (node (ref "U3") (pin "9") (pinfunction "GPIO5/RTC_GPIO5/TOUCH5/ADC1_CH4_9") (pintype "passive"))
    )
    (net (code "29") (name "/GPIO6") (class "Default")
      (node (ref "J4") (pin "9") (pinfunction "9_9") (pintype "passive"))
      (node (ref "U3") (pin "10") (pinfunction "GPIO6/RTC_GPIO6/TOUCH6/ADC1_CH5_10") (pintype "passive"))
    )
    (net (code "30") (name "/GPIO7") (class "Default")
      (node (ref "J4") (pin "10") (pinfunction "10_10") (pintype "passive"))
      (node (ref "U3") (pin "11") (pinfunction "GPIO7/RTC_GPIO7/TOUCH7/ADC1_CH6_11") (pintype "passive"))
    )
    (net (code "31") (name "/GPIO8") (class "Default")
      (node (ref "J4") (pin "11") (pinfunction "11_11") (pintype "passive"))
      (node (ref "U3") (pin "12") (pinfunction "GPIO8/RTC_GPIO8/TOUCH8/ADC1_CH7/SUBSPICS1_12") (pintype "passive"))
    )
    (net (code "32") (name "/GPIO9") (class "Default")
      (node (ref "J4") (pin "12") (pinfunction "12_12") (pintype "passive"))
      (node (ref "U3") (pin "13") (pinfunction "GPIO9/RTC_GPIO9/TOUCH9/ADC1_CH8/FSPIHD/SUBSPIHD_13") (pintype "passive"))
    )
    (net (code "33") (name "/GPIO10") (class "Default")
      (node (ref "J4") (pin "13") (pinfunction "13_13") (pintype "passive"))
      (node (ref "U3") (pin "14") (pinfunction "GPIO10/RTC_GPIO10/TOUCH10/ADC1_CH9/FSPICS0/FSPIIO4/SUBSPICS0_14") (pintype "passive"))
    )
    (net (code "34") (name "/GPIO11") (class "Default")
      (node (ref "J4") (pin "14") (pinfunction "14_14") (pintype "passive"))
      (node (ref "U3") (pin "15") (pinfunction "GPIO11/RTC_GPIO11/TOUCH11/ADC2_CH0/FSPID/FSPIIO5/SUBSPID_15") (pintype "passive"))
    )
    (net (code "35") (name "/GPIO12") (class "Default")
      (node (ref "J4") (pin "15") (pinfunction "15_15") (pintype "passive"))
      (node (ref "U3") (pin "16") (pinfunction "GPIO12/RTC_GPIO12/TOUCH12/ADC2_CH1/FSPICLK/FSPIIO6/SUBSPICLK_16") (pintype "passive"))
    )
    (net (code "36") (name "/GPIO13") (class "Default")
      (node (ref "J4") (pin "16") (pinfunction "16_16") (pintype "passive"))
      (node (ref "U3") (pin "17") (pinfunction "GPIO13/RTC_GPIO13/TOUCH13/ADC2_CH2/FSPIQ/FSPIIO7/SUBSPIQ_17") (pintype "passive"))
    )
    (net (code "37") (name "/GPIO14") (class "Default")
      (node (ref "J4") (pin "17") (pinfunction "17_17") (pintype "passive"))
      (node (ref "U3") (pin "18") (pinfunction "GPIO14/RTC_GPIO14/TOUCH14/ADC2_CH3/FSPIWP/FSPIDQS/SUBSPIWP_18") (pintype "passive"))
    )
    (net (code "38") (name "/GPIO15") (class "Default")
      (node (ref "J4") (pin "18") (pinfunction "18_18") (pintype "passive"))
      (node (ref "U3") (pin "19") (pinfunction "GPIO15/RTC_GPIO15/U0RTS/ADC2_CH4/XTAL_32K_P_19") (pintype "passive"))
    )
    (net (code "39") (name "/GPIO16") (class "Default")
      (node (ref "J4") (pin "19") (pinfunction "19_19") (pintype "passive"))
      (node (ref "U3") (pin "20") (pinfunction "GPIO16/RTC_GPIO16/U0CTS/ADC2_CH5/XTAL_32K_N_20") (pintype "passive"))
    )
    (net (code "40") (name "/GPIO17") (class "Default")
      (node (ref "J4") (pin "20") (pinfunction "20_20") (pintype "passive"))
      (node (ref "U3") (pin "21") (pinfunction "GPIO17/RTC_GPIO17/U1TXD/ADC2_CH6_21") (pintype "passive"))
    )
    (net (code "41") (name "/GPIO18") (class "Default")
      (node (ref "J4") (pin "21") (pinfunction "21_21") (pintype "passive"))
      (node (ref "U3") (pin "22") (pinfunction "GPIO18/RTC_GPIO18/U1RXD/ADC2_CH7/CLK_OUT3_22") (pintype "passive"))
    )
    (net (code "42") (name "/GPIO21") (class "Default")
      (node (ref "J5") (pin "19") (pinfunction "19_19") (pintype "passive"))
      (node (ref "U3") (pin "25") (pinfunction "GPIO21/RTC_GPIO21_25") (pintype "passive"))
    )
    (net (code "43") (name "/GPIO26") (class "Default")
      (node (ref "J5") (pin "18") (pinfunction "18_18") (pintype "passive"))
      (node (ref "U3") (pin "26") (pinfunction "GPIO26/SPICS1_26") (pintype "passive"))
    )
    (net (code "44") (name "/GPIO33") (class "Default")
      (node (ref "J5") (pin "17") (pinfunction "17_17") (pintype "passive"))
      (node (ref "U3") (pin "28") (pinfunction "GPIO33/SPIIO4/FSPIHD/SUBSPIHD_28") (pintype "passive"))
    )
    (net (code "45") (name "/GPIO34") (class "Default")
      (node (ref "J5") (pin "16") (pinfunction "16_16") (pintype "passive"))
      (node (ref "U3") (pin "29") (pinfunction "GPIO34/SPIIO5/FSPICS0/SUBSPICS0_29") (pintype "passive"))
    )
    (net (code "46") (name "/GPIO35") (class "Default")
      (node (ref "J5") (pin "15") (pinfunction "15_15") (pintype "passive"))
      (node (ref "U3") (pin "31") (pinfunction "GPIO35/SPIIO6/FSPID/SUBSPID_31") (pintype "passive"))
    )
    (net (code "47") (name "/GPIO36") (class "Default")
      (node (ref "J5") (pin "14") (pinfunction "14_14") (pintype "passive"))
      (node (ref "U3") (pin "32") (pinfunction "GPIO36/SPIIO7/FSPICLK/SUBSPICLK_32") (pintype "passive"))
    )
    (net (code "48") (name "/GPIO37") (class "Default")
      (node (ref "J5") (pin "13") (pinfunction "13_13") (pintype "passive"))
      (node (ref "U3") (pin "33") (pinfunction "GPIO37/SPIDQS/FSPIQ/SUBSPIQ_33") (pintype "passive"))
    )
    (net (code "49") (name "/GPIO38") (class "Default")
      (node (ref "J5") (pin "12") (pinfunction "12_12") (pintype "passive"))
      (node (ref "U3") (pin "34") (pinfunction "GPIO38/FSPIWP/SUBSPIWP_34") (pintype "passive"))
    )
    (net (code "50") (name "/GPIO39") (class "Default")
      (node (ref "J5") (pin "11") (pinfunction "11_11") (pintype "passive"))
      (node (ref "U3") (pin "35") (pinfunction "MTCK/GPIO39/CLK_OUT3/SUBSPICS1_35") (pintype "passive"))
    )
    (net (code "51") (name "/GPIO40") (class "Default")
      (node (ref "J5") (pin "10") (pinfunction "10_10") (pintype "passive"))
      (node (ref "U3") (pin "36") (pinfunction "MTDO/GPIO40/CLK_OUT2_36") (pintype "passive"))
    )
    (net (code "52") (name "/GPIO41") (class "Default")
      (node (ref "J5") (pin "9") (pinfunction "9_9") (pintype "passive"))
      (node (ref "U3") (pin "37") (pinfunction "MTDI/GPIO41/CLK_OUT1_37") (pintype "passive"))
    )
    (net (code "53") (name "/GPIO42") (class "Default")
      (node (ref "J5") (pin "8") (pinfunction "8_8") (pintype "passive"))
      (node (ref "U3") (pin "38") (pinfunction "MTMS/GPIO42_38") (pintype "passive"))
    )
    (net (code "54") (name "/GPIO45") (class "Default")
      (node (ref "J5") (pin "5") (pinfunction "5_5") (pintype "passive"))
      (node (ref "U3") (pin "41") (pinfunction "GPIO45_41") (pintype "passive"))
    )
    (net (code "55") (name "/GPIO46") (class "Default")
      (node (ref "J5") (pin "4") (pinfunction "4_4") (pintype "passive"))
      (node (ref "U3") (pin "44") (pinfunction "GPIO46_44") (pintype "passive"))
    )
    (net (code "56") (name "/GPIO47") (class "Default")
      (node (ref "J5") (pin "23") (pinfunction "23_23") (pintype "passive"))
      (node (ref "U3") (pin "27") (pinfunction "GPIO47/SPICLK_P_DIFF/SUBSPICLK_P_DIFF_27") (pintype "passive"))
    )
    (net (code "57") (name "/GPIO48") (class "Default")
      (node (ref "J5") (pin "22") (pinfunction "22_22") (pintype "passive"))
      (node (ref "U3") (pin "30") (pinfunction "GPIO48/SPICLK_N_DIFF/SUBSPICLK_N_DIFF_30") (pintype "passive"))
    )
    (net (code "58") (name "/RTS_FTDI") (class "Default")
      (node (ref "Q1") (pin "2") (pinfunction "E_2") (pintype "passive"))
      (node (ref "R22") (pin "2") (pinfunction "2_2") (pintype "passive"))
      (node (ref "U1") (pin "19") (pinfunction "~{RTS}_19") (pintype "passive"))
    )
    (net (code "59") (name "/RXD_FTDI") (class "Default")
      (node (ref "R18") (pin "2") (pinfunction "2_2") (pintype "passive"))
      (node (ref "U1") (pin "1") (pinfunction "RXD_1") (pintype "passive"))
    )
    (net (code "60") (name "/TXD_FTDI") (class "Default")
      (node (ref "R20") (pin "2") (pinfunction "2_2") (pintype "passive"))
      (node (ref "U1") (pin "17") (pinfunction "TXD_17") (pintype "passive"))
    )
    (net (code "61") (name "/U0RXD") (class "Default")
      (node (ref "J5") (pin "6") (pinfunction "6_6") (pintype "passive"))
      (node (ref "R20") (pin "1") (pinfunction "1_1") (pintype "passive"))
      (node (ref "U3") (pin "40") (pinfunction "U0RXD/GPIO44/CLK_OUT2_40") (pintype "passive"))
    )
    (net (code "62") (name "/U0TXD") (class "Default")
      (node (ref "J5") (pin "7") (pinfunction "7_7") (pintype "passive"))
      (node (ref "R18") (pin "1") (pinfunction "1_1") (pintype "passive"))
      (node (ref "U3") (pin "39") (pinfunction "U0TXD/GPIO43/CLK_OUT1_39") (pintype "passive"))
    )
    (net (code "63") (name "/VBUS_SENSE") (class "Default")
      (node (ref "R10") (pin "1") (pinfunction "1_1") (pintype "passive"))
      (node (ref "R13") (pin "2") (pinfunction "2_2") (pintype "passive"))
      (node (ref "U1") (pin "16") (pinfunction "CBUS3_16") (pintype "passive"))
    )
    (net (code "64") (name "GND") (class "Default")
      (node (ref "C1") (pin "1") (pinfunction "1_1") (pintype "passive"))
      (node (ref "C10") (pin "1") (pinfunction "1_1") (pintype "passive"))
      (node (ref "C11") (pin "1") (pinfunction "1_1") (pintype "passive"))
      (node (ref "C12") (pin "1") (pinfunction "1_1") (pintype "passive"))
      (node (ref "C13") (pin "1") (pinfunction "1_1") (pintype "passive"))
      (node (ref "C14") (pin "1") (pinfunction "1_1") (pintype "passive"))
      (node (ref "C15") (pin "1") (pinfunction "1_1") (pintype "passive"))
      (node (ref "C16") (pin "1") (pinfunction "1_1") (pintype "passive"))
      (node (ref "C17") (pin "1") (pinfunction "1_1") (pintype "passive"))
      (node (ref "C2") (pin "1") (pinfunction "1_1") (pintype "passive"))
      (node (ref "C3") (pin "2") (pinfunction "2_2") (pintype "passive"))
      (node (ref "C4") (pin "2") (pinfunction "2_2") (pintype "passive"))
      (node (ref "C5") (pin "2") (pinfunction "2_2") (pintype "passive"))
      (node (ref "C6") (pin "2") (pinfunction "2_2") (pintype "passive"))
      (node (ref "C7") (pin "1") (pinfunction "1_1") (pintype "passive"))
      (node (ref "C8") (pin "1") (pinfunction "1_1") (pintype "passive"))
      (node (ref "C9") (pin "1") (pinfunction "1_1") (pintype "passive"))
      (node (ref "D1") (pin "1") (pinfunction "1_1") (pintype "passive"))
      (node (ref "D3") (pin "1") (pinfunction "1_1") (pintype "passive"))
      (node (ref "D4") (pin "1") (pinfunction "1_1") (pintype "passive"))
      (node (ref "D5") (pin "1") (pinfunction "1_1") (pintype "passive"))
      (node (ref "D6") (pin "1") (pinfunction "1_1") (pintype "passive"))
      (node (ref "D7") (pin "1") (pinfunction "1_1") (pintype "passive"))
      (node (ref "D8") (pin "1") (pinfunction "1_1") (pintype "passive"))
      (node (ref "J1") (pin "A1B12") (pinfunction "GND_A1B12_A1B12") (pintype "passive"))
      (node (ref "J1") (pin "B1A12") (pinfunction "GND_B1A12_B1A12") (pintype "passive"))
      (node (ref "J1") (pin "S1") (pinfunction "SHIELD_1_S1") (pintype "passive"))
      (node (ref "J1") (pin "S2") (pinfunction "SHIELD_2_S2") (pintype "passive"))
      (node (ref "J1") (pin "S3") (pinfunction "SHIELD_3_S3") (pintype "passive"))
      (node (ref "J1") (pin "S4") (pinfunction "SHIELD_4_S4") (pintype "passive"))
      (node (ref "J2") (pin "A1B12") (pinfunction "GND_A1B12_A1B12") (pintype "passive"))
      (node (ref "J2") (pin "B1A12") (pinfunction "GND_B1A12_B1A12") (pintype "passive"))
      (node (ref "J2") (pin "S1") (pinfunction "SHIELD_1_S1") (pintype "passive"))
      (node (ref "J2") (pin "S2") (pinfunction "SHIELD_2_S2") (pintype "passive"))
      (node (ref "J2") (pin "S3") (pinfunction "SHIELD_3_S3") (pintype "passive"))
      (node (ref "J2") (pin "S4") (pinfunction "SHIELD_4_S4") (pintype "passive"))
      (node (ref "J4") (pin "1") (pinfunction "1_1") (pintype "passive"))
      (node (ref "J4") (pin "23") (pinfunction "23_23") (pintype "passive"))
      (node (ref "J4") (pin "24") (pinfunction "24_24") (pintype "passive"))
      (node (ref "J5") (pin "2") (pinfunction "2_2") (pintype "passive"))
      (node (ref "J5") (pin "24") (pinfunction "24_24") (pintype "passive"))
      (node (ref "R11") (pin "1") (pinfunction "1_1") (pintype "passive"))
      (node (ref "R12") (pin "1") (pinfunction "1_1") (pintype "passive"))
      (node (ref "R13") (pin "1") (pinfunction "1_1") (pintype "passive"))
      (node (ref "R14") (pin "1") (pinfunction "1_1") (pintype "passive"))
      (node (ref "R15") (pin "1") (pinfunction "1_1") (pintype "passive"))
      (node (ref "R9") (pin "1") (pinfunction "1_1") (pintype "passive"))
      (node (ref "SW1") (pin "3") (pinfunction "3_3") (pintype "passive"))
      (node (ref "SW1") (pin "4") (pinfunction "4_4") (pintype "passive"))
      (node (ref "SW2") (pin "3") (pinfunction "3_3") (pintype "passive"))
      (node (ref "SW2") (pin "4") (pinfunction "4_4") (pintype "passive"))
      (node (ref "U1") (pin "13") (pinfunction "GND_13") (pintype "passive"))
      (node (ref "U1") (pin "21") (pinfunction "GND_21") (pintype "passive"))
      (node (ref "U1") (pin "3") (pinfunction "GND_3") (pintype "passive"))
      (node (ref "U2") (pin "2") (pinfunction "GND_2") (pintype "power_in"))
      (node (ref "U2") (pin "4") (pinfunction "GND_4") (pintype "power_in"))
      (node (ref "U3") (pin "1") (pinfunction "GND_01_1") (pintype "passive"))
      (node (ref "U3") (pin "2") (pinfunction "GND_02_2") (pintype "passive"))
      (node (ref "U3") (pin "42") (pinfunction "GND_42_42") (pintype "passive"))
      (node (ref "U3") (pin "43") (pinfunction "GND_43_43") (pintype "passive"))
      (node (ref "U3") (pin "46") (pinfunction "GND_46_46") (pintype "passive"))
      (node (ref "U3") (pin "47") (pinfunction "GND_47_47") (pintype "passive"))
      (node (ref "U3") (pin "48") (pinfunction "GND_48_48") (pintype "passive"))
      (node (ref "U3") (pin "49") (pinfunction "GND_49_49") (pintype "passive"))
      (node (ref "U3") (pin "50") (pinfunction "GND_50_50") (pintype "passive"))
      (node (ref "U3") (pin "51") (pinfunction "GND_51_51") (pintype "passive"))
      (node (ref "U3") (pin "52") (pinfunction "GND_52_52") (pintype "passive"))
      (node (ref "U3") (pin "53") (pinfunction "GND_53_53") (pintype "passive"))
      (node (ref "U3") (pin "54") (pinfunction "GND_54_54") (pintype "passive"))
      (node (ref "U3") (pin "55") (pinfunction "GND_55_55") (pintype "passive"))
      (node (ref "U3") (pin "56") (pinfunction "GND_56_56") (pintype "passive"))
      (node (ref "U3") (pin "57") (pinfunction "GND_57_57") (pintype "passive"))
      (node (ref "U3") (pin "58") (pinfunction "GND_58_58") (pintype "passive"))
      (node (ref "U3") (pin "59") (pinfunction "GND_59_59") (pintype "passive"))
      (node (ref "U3") (pin "60") (pinfunction "GND_60_60") (pintype "passive"))
      (node (ref "U3") (pin "61") (pinfunction "GND_61_61") (pintype "passive"))
      (node (ref "U3") (pin "62") (pinfunction "GND_62_62") (pintype "passive"))
      (node (ref "U3") (pin "63") (pinfunction "GND_63_63") (pintype "passive"))
      (node (ref "U3") (pin "64") (pinfunction "GND_64_64") (pintype "passive"))
      (node (ref "U3") (pin "65") (pinfunction "GND_65_65") (pintype "passive"))
      (node (ref "U3") (pin "66") (pinfunction "GND_66_66") (pintype "passive"))
      (node (ref "U3") (pin "67") (pinfunction "GND_67_67") (pintype "passive"))
      (node (ref "U3") (pin "68") (pinfunction "GND_68_68") (pintype "passive"))
      (node (ref "U3") (pin "69") (pinfunction "GND_69_69") (pintype "passive"))
      (node (ref "U3") (pin "70") (pinfunction "GND_70_70") (pintype "passive"))
      (node (ref "U3") (pin "71") (pinfunction "GND_71_71") (pintype "passive"))
      (node (ref "U3") (pin "72") (pinfunction "GND_72_72") (pintype "passive"))
      (node (ref "U3") (pin "73") (pinfunction "GND_73_73") (pintype "passive"))
    )
    (net (code "65") (name "Net-(D1-Pad2)") (class "Default")
      (node (ref "D1") (pin "2") (pinfunction "2_2") (pintype "passive"))
      (node (ref "R3") (pin "1") (pinfunction "1_1") (pintype "passive"))
    )
    (net (code "66") (name "Net-(D2-Pad2)") (class "Default")
      (node (ref "D2") (pin "2") (pinfunction "2_2") (pintype "passive"))
      (node (ref "R4") (pin "1") (pinfunction "1_1") (pintype "passive"))
    )
    (net (code "67") (name "Net-(J1-CC1)") (class "Default")
      (node (ref "J1") (pin "A5") (pinfunction "CC1_A5") (pintype "passive"))
      (node (ref "R12") (pin "2") (pinfunction "2_2") (pintype "passive"))
    )
    (net (code "68") (name "Net-(J1-CC2)") (class "Default")
      (node (ref "J1") (pin "B5") (pinfunction "CC2_B5") (pintype "passive"))
      (node (ref "R11") (pin "2") (pinfunction "2_2") (pintype "passive"))
    )
    (net (code "69") (name "Net-(J2-CC1)") (class "Default")
      (node (ref "J2") (pin "A5") (pinfunction "CC1_A5") (pintype "passive"))
      (node (ref "R15") (pin "2") (pinfunction "2_2") (pintype "passive"))
    )
    (net (code "70") (name "Net-(J2-CC2)") (class "Default")
      (node (ref "J2") (pin "B5") (pinfunction "CC2_B5") (pintype "passive"))
      (node (ref "R14") (pin "2") (pinfunction "2_2") (pintype "passive"))
    )
    (net (code "71") (name "Net-(Q1-B)") (class "Default")
      (node (ref "Q1") (pin "1") (pinfunction "B_1") (pintype "passive"))
      (node (ref "R21") (pin "1") (pinfunction "1_1") (pintype "passive"))
    )
    (net (code "72") (name "Net-(Q2-B)") (class "Default")
      (node (ref "Q2") (pin "1") (pinfunction "B_1") (pintype "passive"))
      (node (ref "R22") (pin "1") (pinfunction "1_1") (pintype "passive"))
    )
    (net (code "73") (name "Net-(U1-CBUS0)") (class "Default")
      (node (ref "R9") (pin "2") (pinfunction "2_2") (pintype "passive"))
      (node (ref "U1") (pin "15") (pinfunction "CBUS0_15") (pintype "passive"))
    )
    (net (code "74") (name "unconnected-(J1-SBUS1-PadA8)") (class "Default")
      (node (ref "J1") (pin "A8") (pinfunction "SBUS1_A8") (pintype "passive+no_connect"))
    )
    (net (code "75") (name "unconnected-(J1-SBUS2-PadB8)") (class "Default")
      (node (ref "J1") (pin "B8") (pinfunction "SBUS2_B8") (pintype "passive+no_connect"))
    )
    (net (code "76") (name "unconnected-(J2-SBUS1-PadA8)") (class "Default")
      (node (ref "J2") (pin "A8") (pinfunction "SBUS1_A8") (pintype "passive+no_connect"))
    )
    (net (code "77") (name "unconnected-(J2-SBUS2-PadB8)") (class "Default")
      (node (ref "J2") (pin "B8") (pinfunction "SBUS2_B8") (pintype "passive+no_connect"))
    )
    (net (code "78") (name "unconnected-(U1-CBUS1-Pad14)") (class "Default")
      (node (ref "U1") (pin "14") (pinfunction "CBUS1_14") (pintype "passive+no_connect"))
    )
    (net (code "79") (name "unconnected-(U1-CBUS2-Pad7)") (class "Default")
      (node (ref "U1") (pin "7") (pinfunction "CBUS2_7") (pintype "passive+no_connect"))
    )
    (net (code "80") (name "unconnected-(U1-~{CTS}-Pad6)") (class "Default")
      (node (ref "U1") (pin "6") (pinfunction "~{CTS}_6") (pintype "passive+no_connect"))
    )
    (net (code "81") (name "unconnected-(U1-~{DCD}-Pad5)") (class "Default")
      (node (ref "U1") (pin "5") (pinfunction "~{DCD}_5") (pintype "passive+no_connect"))
    )
    (net (code "82") (name "unconnected-(U1-~{DSR}-Pad4)") (class "Default")
      (node (ref "U1") (pin "4") (pinfunction "~{DSR}_4") (pintype "passive+no_connect"))
    )
    (net (code "83") (name "unconnected-(U1-~{RI}-Pad2)") (class "Default")
      (node (ref "U1") (pin "2") (pinfunction "~{RI}_2") (pintype "passive+no_connect"))
    )
  )
)
